# 3_Microcontroller_USB_Expansion_Buttons_.net
KiCad netlist of a schematic drawn in Altium Designer
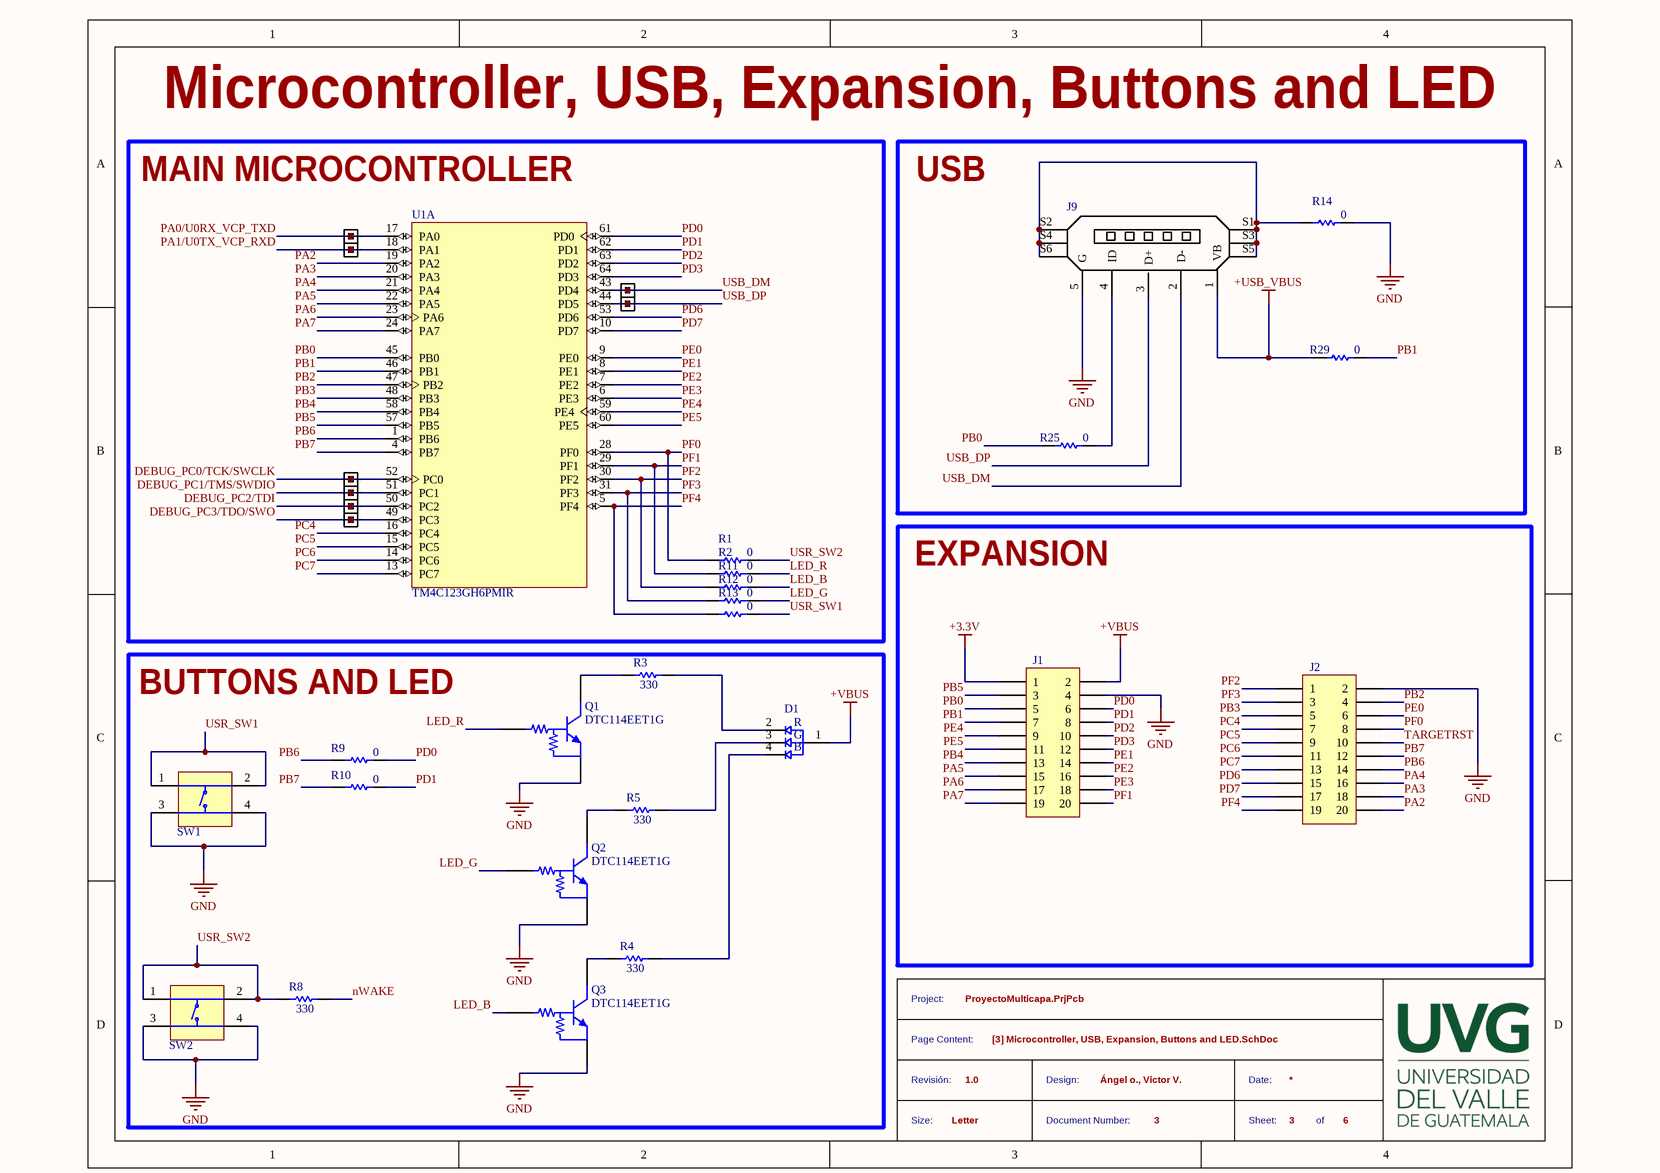
[diagram p0: [3] Microcontroller, USB, Expansion, Buttons and LED.SchDoc]

(export (version "E")
  (design (tool "Eeschema 10.0.6"))
  (components
    (comp (ref "D1")
      (value "RSGHBHC1")
      (footprint "RGB LED")
      (description "RGB LED")
      (fields
        (field (name "MANUFACTURER_PART_NUMBER") "SMLP34RGB2W3")
        (field (name "MOUSER PART NUMBER") "755-SMLP34RGB2W3")
      )
      (libsource (lib "Components") (part "RSGHBHC1"))
    )
    (comp (ref "J1")
      (value "Header 20")
      (footprint "HDR2X10")
      (description "Conn Socket Strip SKT 20 POS 2.54mm Solder ST Thru-Hole")
      (fields
        (field (name "MANUFACTURER") "Samtec")
        (field (name "MANUFACTURER PART NUMBER") "SSW-110-23-S-D")
      )
      (libsource (lib "LiberiaTivaC") (part "SSW-110-23-S-D"))
    )
    (comp (ref "J2")
      (value "Header 20")
      (footprint "HDR2X10")
      (description "Conn Socket Strip SKT 20 POS 2.54mm Solder ST Thru-Hole")
      (fields
        (field (name "MANUFACTURER") "Samtec")
        (field (name "MANUFACTURER PART NUMBER") "SSW-110-23-S-D")
      )
      (libsource (lib "LiberiaTivaC") (part "SSW-110-23-S-D"))
    )
    (comp (ref "J9")
      (value "ZX62-B-5PA")
      (footprint "ZX62B5PA")
      (description "USB Connectors MICRO B RECEPT RA SMT BTTM MNT")
      (fields
        (field (name "MANUFACTURER") "Hirose")
        (field (name "MANUFACTURER PART NUMBER") "ZX62-B-5PA(11)")
      )
      (libsource (lib "LiberiaTivaC") (part "ZX62-B-5PA"))
    )
    (comp (ref "P1") (value "header") (footprint "HEADER 1") (libsource (lib "LiberiaTivaC") (part "header")))
    (comp (ref "P2") (value "header") (footprint "HEADER 1") (libsource (lib "LiberiaTivaC") (part "header")))
    (comp (ref "P3") (value "header") (footprint "HEADER 1") (libsource (lib "LiberiaTivaC") (part "header")))
    (comp (ref "P4") (value "header") (footprint "HEADER 1") (libsource (lib "LiberiaTivaC") (part "header")))
    (comp (ref "P5") (value "header") (footprint "HEADER 1") (libsource (lib "LiberiaTivaC") (part "header")))
    (comp (ref "P6") (value "header") (footprint "HEADER 1") (libsource (lib "LiberiaTivaC") (part "header")))
    (comp (ref "P7") (value "header") (footprint "HEADER 1") (libsource (lib "LiberiaTivaC") (part "header")))
    (comp (ref "P8") (value "header") (footprint "HEADER 1") (libsource (lib "LiberiaTivaC") (part "header")))
    (comp (ref "Q1")
      (value "DTC114EET1G")
      (footprint "ONSC-SC-75-3-463-01_V")
      (description "Trans Digital BJT NPN 50V 100mA 3-Pin SOT-416 T/R")
      (fields (field (name "MANUFACTURER") "ON Semiconductor"))
      (libsource (lib "LiberiaTivaC") (part "DTC114EET1G"))
    )
    (comp (ref "Q2")
      (value "DTC114EET1G")
      (footprint "ONSC-SC-75-3-463-01_V")
      (description "Trans Digital BJT NPN 50V 100mA 3-Pin SOT-416 T/R")
      (fields (field (name "MANUFACTURER") "ON Semiconductor"))
      (libsource (lib "LiberiaTivaC") (part "DTC114EET1G"))
    )
    (comp (ref "Q3")
      (value "DTC114EET1G")
      (footprint "ONSC-SC-75-3-463-01_V")
      (description "Trans Digital BJT NPN 50V 100mA 3-Pin SOT-416 T/R")
      (fields (field (name "MANUFACTURER") "ON Semiconductor"))
      (libsource (lib "LiberiaTivaC") (part "DTC114EET1G"))
    )
    (comp (ref "R1")
      (value "ERJ-3GEY0R00V")
      (footprint "FP-ERJ-3GEY0R00V-IPC_A")
      (description "Res Thick Film 0603 0 Ohm Jumper Molded SMD Punched Carrier T/R")
      (fields (field (name "MANUFACTURER") "Panasonic") (field (name "TOLERANCE") "0%"))
      (libsource (lib "Components") (part "ERJ-3GEY0R00V"))
    )
    (comp (ref "R2")
      (value "ERJ-3GEY0R00V")
      (footprint "FP-ERJ-3GEY0R00V-IPC_A")
      (description "Res Thick Film 0603 0 Ohm Jumper Molded SMD Punched Carrier T/R")
      (fields (field (name "MANUFACTURER") "Panasonic") (field (name "TOLERANCE") "0%"))
      (libsource (lib "Components") (part "ERJ-3GEY0R00V"))
    )
    (comp (ref "R3")
      (value "RC0402FR-07330RL")
      (footprint "RESC1005X40X25LL05T10")
      (description "Res Thick Film 0402 330 Ohm 1% 0.063W(1/16W) ±100ppm/C Pad SMD T/R")
      (fields (field (name "MANUFACTURER") "Yageo / Phycomp") (field (name "TOLERANCE") "1%"))
      (libsource (lib "LiberiaTivaC") (part "RC0402FR-07330RL"))
    )
    (comp (ref "R4")
      (value "RC0402FR-07330RL")
      (footprint "RESC1005X40X25LL05T10")
      (description "Res Thick Film 0402 330 Ohm 1% 0.063W(1/16W) ±100ppm/C Pad SMD T/R")
      (fields (field (name "MANUFACTURER") "Yageo / Phycomp") (field (name "TOLERANCE") "1%"))
      (libsource (lib "LiberiaTivaC") (part "RC0402FR-07330RL"))
    )
    (comp (ref "R5")
      (value "RC0402FR-07330RL")
      (footprint "RESC1005X40X25LL05T10")
      (description "Res Thick Film 0402 330 Ohm 1% 0.063W(1/16W) ±100ppm/C Pad SMD T/R")
      (fields (field (name "MANUFACTURER") "Yageo / Phycomp") (field (name "TOLERANCE") "1%"))
      (libsource (lib "LiberiaTivaC") (part "RC0402FR-07330RL"))
    )
    (comp (ref "R8")
      (value "RC0402FR-07330RL")
      (footprint "RESC1005X40X25LL05T10")
      (description "Res Thick Film 0402 330 Ohm 1% 0.063W(1/16W) ±100ppm/C Pad SMD T/R")
      (fields (field (name "MANUFACTURER") "Yageo / Phycomp") (field (name "TOLERANCE") "1%"))
      (libsource (lib "LiberiaTivaC") (part "RC0402FR-07330RL"))
    )
    (comp (ref "R9")
      (value "ERJ-3GEY0R00V")
      (footprint "FP-ERJ-3GEY0R00V-IPC_A")
      (description "Res Thick Film 0603 0 Ohm Jumper Molded SMD Punched Carrier T/R")
      (fields (field (name "MANUFACTURER") "Panasonic") (field (name "TOLERANCE") "0%"))
      (libsource (lib "Components") (part "ERJ-3GEY0R00V"))
    )
    (comp (ref "R10")
      (value "ERJ-3GEY0R00V")
      (footprint "FP-ERJ-3GEY0R00V-IPC_A")
      (description "Res Thick Film 0603 0 Ohm Jumper Molded SMD Punched Carrier T/R")
      (fields (field (name "MANUFACTURER") "Panasonic") (field (name "TOLERANCE") "0%"))
      (libsource (lib "Components") (part "ERJ-3GEY0R00V"))
    )
    (comp (ref "R11")
      (value "ERJ-3GEY0R00V")
      (footprint "FP-ERJ-3GEY0R00V-IPC_A")
      (description "Res Thick Film 0603 0 Ohm Jumper Molded SMD Punched Carrier T/R")
      (fields (field (name "MANUFACTURER") "Panasonic") (field (name "TOLERANCE") "0%"))
      (libsource (lib "Components") (part "ERJ-3GEY0R00V"))
    )
    (comp (ref "R12")
      (value "ERJ-3GEY0R00V")
      (footprint "FP-ERJ-3GEY0R00V-IPC_A")
      (description "Res Thick Film 0603 0 Ohm Jumper Molded SMD Punched Carrier T/R")
      (fields (field (name "MANUFACTURER") "Panasonic") (field (name "TOLERANCE") "0%"))
      (libsource (lib "Components") (part "ERJ-3GEY0R00V"))
    )
    (comp (ref "R13")
      (value "ERJ-3GEY0R00V")
      (footprint "FP-ERJ-3GEY0R00V-IPC_A")
      (description "Res Thick Film 0603 0 Ohm Jumper Molded SMD Punched Carrier T/R")
      (fields (field (name "MANUFACTURER") "Panasonic") (field (name "TOLERANCE") "0%"))
      (libsource (lib "Components") (part "ERJ-3GEY0R00V"))
    )
    (comp (ref "R14")
      (value "ERJ-3GEY0R00V")
      (footprint "FP-ERJ-3GEY0R00V-IPC_A")
      (description "Res Thick Film 0603 0 Ohm Jumper Molded SMD Punched Carrier T/R")
      (fields (field (name "MANUFACTURER") "Panasonic") (field (name "TOLERANCE") "0%"))
      (libsource (lib "Components") (part "ERJ-3GEY0R00V"))
    )
    (comp (ref "R25")
      (value "ERJ-3GEY0R00V")
      (footprint "FP-ERJ-3GEY0R00V-IPC_A")
      (description "Res Thick Film 0603 0 Ohm Jumper Molded SMD Punched Carrier T/R")
      (fields (field (name "MANUFACTURER") "Panasonic") (field (name "TOLERANCE") "0%"))
      (libsource (lib "Components") (part "ERJ-3GEY0R00V"))
    )
    (comp (ref "R29")
      (value "ERJ-3GEY0R00V")
      (footprint "FP-ERJ-3GEY0R00V-IPC_A")
      (description "Res Thick Film 0603 0 Ohm Jumper Molded SMD Punched Carrier T/R")
      (fields (field (name "MANUFACTURER") "Panasonic") (field (name "TOLERANCE") "0%"))
      (libsource (lib "Components") (part "ERJ-3GEY0R00V"))
    )
    (comp (ref "SW1")
      (value "B3S-1000")
      (footprint "OMRON-B3S-1000-4_V")
      (description "Sealed Tactile Switch, SPST-NO, 3 to 24 V, -25 to 70 degC, 4-Pin SMD, RoHS, Bulk")
      (fields (field (name "MANUFACTURER") "Omron"))
      (libsource (lib "LiberiaTivaC") (part "B3S-1000"))
    )
    (comp (ref "SW2")
      (value "B3S-1000")
      (footprint "OMRON-B3S-1000-4_V")
      (description "Sealed Tactile Switch, SPST-NO, 3 to 24 V, -25 to 70 degC, 4-Pin SMD, RoHS, Bulk")
      (fields (field (name "MANUFACTURER") "Omron"))
      (libsource (lib "LiberiaTivaC") (part "B3S-1000"))
    )
    (comp (ref "U1")
      (value "TM4C123GH6PMIR")
      (footprint "PM0064A_L")
      (fields (field (name "MANUFACTURER") "Texas Instruments"))
      (libsource (lib "LiberiaTivaC") (part "TM4C123GH6PMI"))
    )
  )
  (nets
    (net (code "1") (name "+3.3V") (class "Default")
      (node (ref "J1") (pin "1") (pinfunction "1_1") (pintype "passive"))
    )
    (net (code "2") (name "+USB_VBUS") (class "Default")
      (node (ref "J9") (pin "1") (pinfunction "VB_1") (pintype "passive"))
      (node (ref "R29") (pin "1") (pinfunction "1_1") (pintype "passive"))
    )
    (net (code "3") (name "+VBUS") (class "Default")
      (node (ref "D1") (pin "1") (pinfunction "A_1") (pintype "passive"))
      (node (ref "J1") (pin "2") (pinfunction "2_2") (pintype "passive"))
    )
    (net (code "4") (name "/DEBUG_PC0{slash}TCK{slash}SWCLK") (class "Default")
      (node (ref "P3") (pin "1") (pinfunction "1_1") (pintype "passive"))
      (node (ref "U1") (pin "52") (pinfunction "PC0_52") (pintype "bidirectional"))
    )
    (net (code "5") (name "/DEBUG_PC1{slash}TMS{slash}SWDIO") (class "Default")
      (node (ref "P4") (pin "1") (pinfunction "1_1") (pintype "passive"))
      (node (ref "U1") (pin "51") (pinfunction "PC1_51") (pintype "bidirectional"))
    )
    (net (code "6") (name "/DEBUG_PC2{slash}TDI") (class "Default")
      (node (ref "P5") (pin "1") (pinfunction "1_1") (pintype "passive"))
      (node (ref "U1") (pin "50") (pinfunction "PC2_50") (pintype "bidirectional"))
    )
    (net (code "7") (name "/DEBUG_PC3{slash}TDO{slash}SWO") (class "Default")
      (node (ref "P6") (pin "1") (pinfunction "1_1") (pintype "passive"))
      (node (ref "U1") (pin "49") (pinfunction "PC3_49") (pintype "bidirectional"))
    )
    (net (code "8") (name "/LED_B") (class "Default")
      (node (ref "Q3") (pin "1") (pinfunction "B_1") (pintype "passive"))
      (node (ref "R11") (pin "2") (pinfunction "2_2") (pintype "passive"))
    )
    (net (code "9") (name "/LED_G") (class "Default")
      (node (ref "Q2") (pin "1") (pinfunction "B_1") (pintype "passive"))
      (node (ref "R12") (pin "2") (pinfunction "2_2") (pintype "passive"))
    )
    (net (code "10") (name "/LED_R") (class "Default")
      (node (ref "Q1") (pin "1") (pinfunction "B_1") (pintype "passive"))
      (node (ref "R2") (pin "2") (pinfunction "2_2") (pintype "passive"))
    )
    (net (code "11") (name "/PA0{slash}U0RX_VCP_TXD") (class "Default")
      (node (ref "P1") (pin "1") (pinfunction "1_1") (pintype "passive"))
      (node (ref "U1") (pin "17") (pinfunction "PA0_17") (pintype "bidirectional"))
    )
    (net (code "12") (name "/PA1{slash}U0TX_VCP_RXD") (class "Default")
      (node (ref "P2") (pin "1") (pinfunction "1_1") (pintype "passive"))
      (node (ref "U1") (pin "18") (pinfunction "PA1_18") (pintype "bidirectional"))
    )
    (net (code "13") (name "/PA2") (class "Default")
      (node (ref "J2") (pin "20") (pinfunction "20_20") (pintype "passive"))
      (node (ref "U1") (pin "19") (pinfunction "PA2_19") (pintype "bidirectional"))
    )
    (net (code "14") (name "/PA3") (class "Default")
      (node (ref "J2") (pin "18") (pinfunction "18_18") (pintype "passive"))
      (node (ref "U1") (pin "20") (pinfunction "PA3_20") (pintype "bidirectional"))
    )
    (net (code "15") (name "/PA4") (class "Default")
      (node (ref "J2") (pin "16") (pinfunction "16_16") (pintype "passive"))
      (node (ref "U1") (pin "21") (pinfunction "PA4_21") (pintype "bidirectional"))
    )
    (net (code "16") (name "/PA5") (class "Default")
      (node (ref "J1") (pin "15") (pinfunction "15_15") (pintype "passive"))
      (node (ref "U1") (pin "22") (pinfunction "PA5_22") (pintype "bidirectional"))
    )
    (net (code "17") (name "/PA6") (class "Default")
      (node (ref "J1") (pin "17") (pinfunction "17_17") (pintype "passive"))
      (node (ref "U1") (pin "23") (pinfunction "PA6_23") (pintype "bidirectional"))
    )
    (net (code "18") (name "/PA7") (class "Default")
      (node (ref "J1") (pin "19") (pinfunction "19_19") (pintype "passive"))
      (node (ref "U1") (pin "24") (pinfunction "PA7_24") (pintype "bidirectional"))
    )
    (net (code "19") (name "/PB0") (class "Default")
      (node (ref "J1") (pin "5") (pinfunction "5_5") (pintype "passive"))
      (node (ref "R25") (pin "1") (pinfunction "1_1") (pintype "passive"))
      (node (ref "U1") (pin "45") (pinfunction "PB0_45") (pintype "bidirectional"))
    )
    (net (code "20") (name "/PB1") (class "Default")
      (node (ref "J1") (pin "7") (pinfunction "7_7") (pintype "passive"))
      (node (ref "R29") (pin "2") (pinfunction "2_2") (pintype "passive"))
      (node (ref "U1") (pin "46") (pinfunction "PB1_46") (pintype "bidirectional"))
    )
    (net (code "21") (name "/PB2") (class "Default")
      (node (ref "J2") (pin "4") (pinfunction "4_4") (pintype "passive"))
      (node (ref "U1") (pin "47") (pinfunction "PB2_47") (pintype "bidirectional"))
    )
    (net (code "22") (name "/PB3") (class "Default")
      (node (ref "J2") (pin "5") (pinfunction "5_5") (pintype "passive"))
      (node (ref "U1") (pin "48") (pinfunction "PB3_48") (pintype "bidirectional"))
    )
    (net (code "23") (name "/PB4") (class "Default")
      (node (ref "J1") (pin "13") (pinfunction "13_13") (pintype "passive"))
      (node (ref "U1") (pin "58") (pinfunction "PB4_58") (pintype "bidirectional"))
    )
    (net (code "24") (name "/PB5") (class "Default")
      (node (ref "J1") (pin "3") (pinfunction "3_3") (pintype "passive"))
      (node (ref "U1") (pin "57") (pinfunction "PB5_57") (pintype "bidirectional"))
    )
    (net (code "25") (name "/PB6") (class "Default")
      (node (ref "J2") (pin "14") (pinfunction "14_14") (pintype "passive"))
      (node (ref "R9") (pin "1") (pinfunction "1_1") (pintype "passive"))
      (node (ref "U1") (pin "1") (pinfunction "PB6_1") (pintype "bidirectional"))
    )
    (net (code "26") (name "/PB7") (class "Default")
      (node (ref "J2") (pin "12") (pinfunction "12_12") (pintype "passive"))
      (node (ref "R10") (pin "1") (pinfunction "1_1") (pintype "passive"))
      (node (ref "U1") (pin "4") (pinfunction "PB7_4") (pintype "bidirectional"))
    )
    (net (code "27") (name "/PC4") (class "Default")
      (node (ref "J2") (pin "7") (pinfunction "7_7") (pintype "passive"))
      (node (ref "U1") (pin "16") (pinfunction "PC4_16") (pintype "bidirectional"))
    )
    (net (code "28") (name "/PC5") (class "Default")
      (node (ref "J2") (pin "9") (pinfunction "9_9") (pintype "passive"))
      (node (ref "U1") (pin "15") (pinfunction "PC5_15") (pintype "bidirectional"))
    )
    (net (code "29") (name "/PC6") (class "Default")
      (node (ref "J2") (pin "11") (pinfunction "11_11") (pintype "passive"))
      (node (ref "U1") (pin "14") (pinfunction "PC6_14") (pintype "bidirectional"))
    )
    (net (code "30") (name "/PC7") (class "Default")
      (node (ref "J2") (pin "13") (pinfunction "13_13") (pintype "passive"))
      (node (ref "U1") (pin "13") (pinfunction "PC7_13") (pintype "bidirectional"))
    )
    (net (code "31") (name "/PD0") (class "Default")
      (node (ref "J1") (pin "6") (pinfunction "6_6") (pintype "passive"))
      (node (ref "R9") (pin "2") (pinfunction "2_2") (pintype "passive"))
      (node (ref "U1") (pin "61") (pinfunction "PD0_61") (pintype "bidirectional"))
    )
    (net (code "32") (name "/PD1") (class "Default")
      (node (ref "J1") (pin "8") (pinfunction "8_8") (pintype "passive"))
      (node (ref "R10") (pin "2") (pinfunction "2_2") (pintype "passive"))
      (node (ref "U1") (pin "62") (pinfunction "PD1_62") (pintype "bidirectional"))
    )
    (net (code "33") (name "/PD2") (class "Default")
      (node (ref "J1") (pin "10") (pinfunction "10_10") (pintype "passive"))
      (node (ref "U1") (pin "63") (pinfunction "PD2_63") (pintype "bidirectional"))
    )
    (net (code "34") (name "/PD3") (class "Default")
      (node (ref "J1") (pin "12") (pinfunction "12_12") (pintype "passive"))
      (node (ref "U1") (pin "64") (pinfunction "PD3_64") (pintype "bidirectional"))
    )
    (net (code "35") (name "/PD6") (class "Default")
      (node (ref "J2") (pin "15") (pinfunction "15_15") (pintype "passive"))
      (node (ref "U1") (pin "53") (pinfunction "PD6_53") (pintype "bidirectional"))
    )
    (net (code "36") (name "/PD7") (class "Default")
      (node (ref "J2") (pin "17") (pinfunction "17_17") (pintype "passive"))
      (node (ref "U1") (pin "10") (pinfunction "PD7_10") (pintype "bidirectional"))
    )
    (net (code "37") (name "/PE0") (class "Default")
      (node (ref "J2") (pin "6") (pinfunction "6_6") (pintype "passive"))
      (node (ref "U1") (pin "9") (pinfunction "PE0_9") (pintype "bidirectional"))
    )
    (net (code "38") (name "/PE1") (class "Default")
      (node (ref "J1") (pin "14") (pinfunction "14_14") (pintype "passive"))
      (node (ref "U1") (pin "8") (pinfunction "PE1_8") (pintype "bidirectional"))
    )
    (net (code "39") (name "/PE2") (class "Default")
      (node (ref "J1") (pin "16") (pinfunction "16_16") (pintype "passive"))
      (node (ref "U1") (pin "7") (pinfunction "PE2_7") (pintype "bidirectional"))
    )
    (net (code "40") (name "/PE3") (class "Default")
      (node (ref "J1") (pin "18") (pinfunction "18_18") (pintype "passive"))
      (node (ref "U1") (pin "6") (pinfunction "PE3_6") (pintype "bidirectional"))
    )
    (net (code "41") (name "/PE4") (class "Default")
      (node (ref "J1") (pin "9") (pinfunction "9_9") (pintype "passive"))
      (node (ref "U1") (pin "59") (pinfunction "PE4_59") (pintype "bidirectional"))
    )
    (net (code "42") (name "/PE5") (class "Default")
      (node (ref "J1") (pin "11") (pinfunction "11_11") (pintype "passive"))
      (node (ref "U1") (pin "60") (pinfunction "PE5_60") (pintype "bidirectional"))
    )
    (net (code "43") (name "/PF0") (class "Default")
      (node (ref "J2") (pin "8") (pinfunction "8_8") (pintype "passive"))
      (node (ref "R1") (pin "1") (pinfunction "1_1") (pintype "passive"))
      (node (ref "U1") (pin "28") (pinfunction "PF0_28") (pintype "bidirectional"))
    )
    (net (code "44") (name "/PF1") (class "Default")
      (node (ref "J1") (pin "20") (pinfunction "20_20") (pintype "passive"))
      (node (ref "R2") (pin "1") (pinfunction "1_1") (pintype "passive"))
      (node (ref "U1") (pin "29") (pinfunction "PF1_29") (pintype "bidirectional"))
    )
    (net (code "45") (name "/PF2") (class "Default")
      (node (ref "J2") (pin "1") (pinfunction "1_1") (pintype "passive"))
      (node (ref "R11") (pin "1") (pinfunction "1_1") (pintype "passive"))
      (node (ref "U1") (pin "30") (pinfunction "PF2_30") (pintype "bidirectional"))
    )
    (net (code "46") (name "/PF3") (class "Default")
      (node (ref "J2") (pin "3") (pinfunction "3_3") (pintype "passive"))
      (node (ref "R12") (pin "1") (pinfunction "1_1") (pintype "passive"))
      (node (ref "U1") (pin "31") (pinfunction "PF3_31") (pintype "bidirectional"))
    )
    (net (code "47") (name "/PF4") (class "Default")
      (node (ref "J2") (pin "19") (pinfunction "19_19") (pintype "passive"))
      (node (ref "R13") (pin "1") (pinfunction "1_1") (pintype "passive"))
      (node (ref "U1") (pin "5") (pinfunction "PF4_5") (pintype "bidirectional"))
    )
    (net (code "48") (name "/TARGETRST") (class "Default")
      (node (ref "J2") (pin "10") (pinfunction "10_10") (pintype "passive"))
    )
    (net (code "49") (name "/USB_DM") (class "Default")
      (node (ref "J9") (pin "2") (pinfunction "D-_2") (pintype "passive"))
      (node (ref "P7") (pin "1") (pinfunction "1_1") (pintype "passive"))
      (node (ref "U1") (pin "43") (pinfunction "PD4_43") (pintype "bidirectional"))
    )
    (net (code "50") (name "/USB_DP") (class "Default")
      (node (ref "J9") (pin "3") (pinfunction "D+_3") (pintype "passive"))
      (node (ref "P8") (pin "1") (pinfunction "1_1") (pintype "passive"))
      (node (ref "U1") (pin "44") (pinfunction "PD5_44") (pintype "bidirectional"))
    )
    (net (code "51") (name "/USR_SW1") (class "Default")
      (node (ref "R13") (pin "2") (pinfunction "2_2") (pintype "passive"))
      (node (ref "SW1") (pin "1") (pinfunction "1_1") (pintype "passive"))
      (node (ref "SW1") (pin "2") (pinfunction "2_2") (pintype "passive"))
    )
    (net (code "52") (name "/USR_SW2") (class "Default")
      (node (ref "R1") (pin "2") (pinfunction "2_2") (pintype "passive"))
      (node (ref "R8") (pin "1") (pinfunction "1_1") (pintype "passive"))
      (node (ref "SW2") (pin "1") (pinfunction "1_1") (pintype "passive"))
      (node (ref "SW2") (pin "2") (pinfunction "2_2") (pintype "passive"))
    )
    (net (code "53") (name "/nWAKE") (class "Default")
      (node (ref "R8") (pin "2") (pinfunction "2_2") (pintype "passive"))
    )
    (net (code "54") (name "GND") (class "Default")
      (node (ref "J1") (pin "4") (pinfunction "4_4") (pintype "passive"))
      (node (ref "J2") (pin "2") (pinfunction "2_2") (pintype "passive"))
      (node (ref "J9") (pin "5") (pinfunction "G_5") (pintype "passive"))
      (node (ref "Q1") (pin "2") (pinfunction "E_2") (pintype "passive"))
      (node (ref "Q2") (pin "2") (pinfunction "E_2") (pintype "passive"))
      (node (ref "Q3") (pin "2") (pinfunction "E_2") (pintype "passive"))
      (node (ref "R14") (pin "2") (pinfunction "2_2") (pintype "passive"))
      (node (ref "SW1") (pin "3") (pinfunction "3_3") (pintype "passive"))
      (node (ref "SW1") (pin "4") (pinfunction "4_4") (pintype "passive"))
      (node (ref "SW2") (pin "3") (pinfunction "3_3") (pintype "passive"))
      (node (ref "SW2") (pin "4") (pinfunction "4_4") (pintype "passive"))
    )
    (net (code "55") (name "Net-(D1-B)") (class "Default")
      (node (ref "D1") (pin "4") (pinfunction "B_4") (pintype "passive"))
      (node (ref "R4") (pin "2") (pinfunction "2_2") (pintype "passive"))
    )
    (net (code "56") (name "Net-(D1-G)") (class "Default")
      (node (ref "D1") (pin "3") (pinfunction "G_3") (pintype "passive"))
      (node (ref "R5") (pin "2") (pinfunction "2_2") (pintype "passive"))
    )
    (net (code "57") (name "Net-(D1-R)") (class "Default")
      (node (ref "D1") (pin "2") (pinfunction "R_2") (pintype "passive"))
      (node (ref "R3") (pin "2") (pinfunction "2_2") (pintype "passive"))
    )
    (net (code "58") (name "Net-(J9-ID)") (class "Default")
      (node (ref "J9") (pin "4") (pinfunction "ID_4") (pintype "passive"))
      (node (ref "R25") (pin "2") (pinfunction "2_2") (pintype "passive"))
    )
    (net (code "59") (name "Net-(J9-PadS1)") (class "Default")
      (node (ref "J9") (pin "S1") (pinfunction "S1_S1") (pintype "passive"))
      (node (ref "J9") (pin "S2") (pinfunction "S2_S2") (pintype "passive"))
      (node (ref "J9") (pin "S3") (pinfunction "S3_S3") (pintype "passive"))
      (node (ref "J9") (pin "S4") (pinfunction "S4_S4") (pintype "passive"))
      (node (ref "J9") (pin "S5") (pinfunction "S5_S5") (pintype "passive"))
      (node (ref "J9") (pin "S6") (pinfunction "S6_S6") (pintype "passive"))
      (node (ref "R14") (pin "1") (pinfunction "1_1") (pintype "passive"))
    )
    (net (code "60") (name "Net-(Q1-C)") (class "Default")
      (node (ref "Q1") (pin "3") (pinfunction "C_3") (pintype "passive"))
      (node (ref "R3") (pin "1") (pinfunction "1_1") (pintype "passive"))
    )
    (net (code "61") (name "Net-(Q2-C)") (class "Default")
      (node (ref "Q2") (pin "3") (pinfunction "C_3") (pintype "passive"))
      (node (ref "R5") (pin "1") (pinfunction "1_1") (pintype "passive"))
    )
    (net (code "62") (name "Net-(Q3-C)") (class "Default")
      (node (ref "Q3") (pin "3") (pinfunction "C_3") (pintype "passive"))
      (node (ref "R4") (pin "1") (pinfunction "1_1") (pintype "passive"))
    )
  )
)
